# mb_01-1.net
KiCad netlist of a schematic drawn in EAGLE
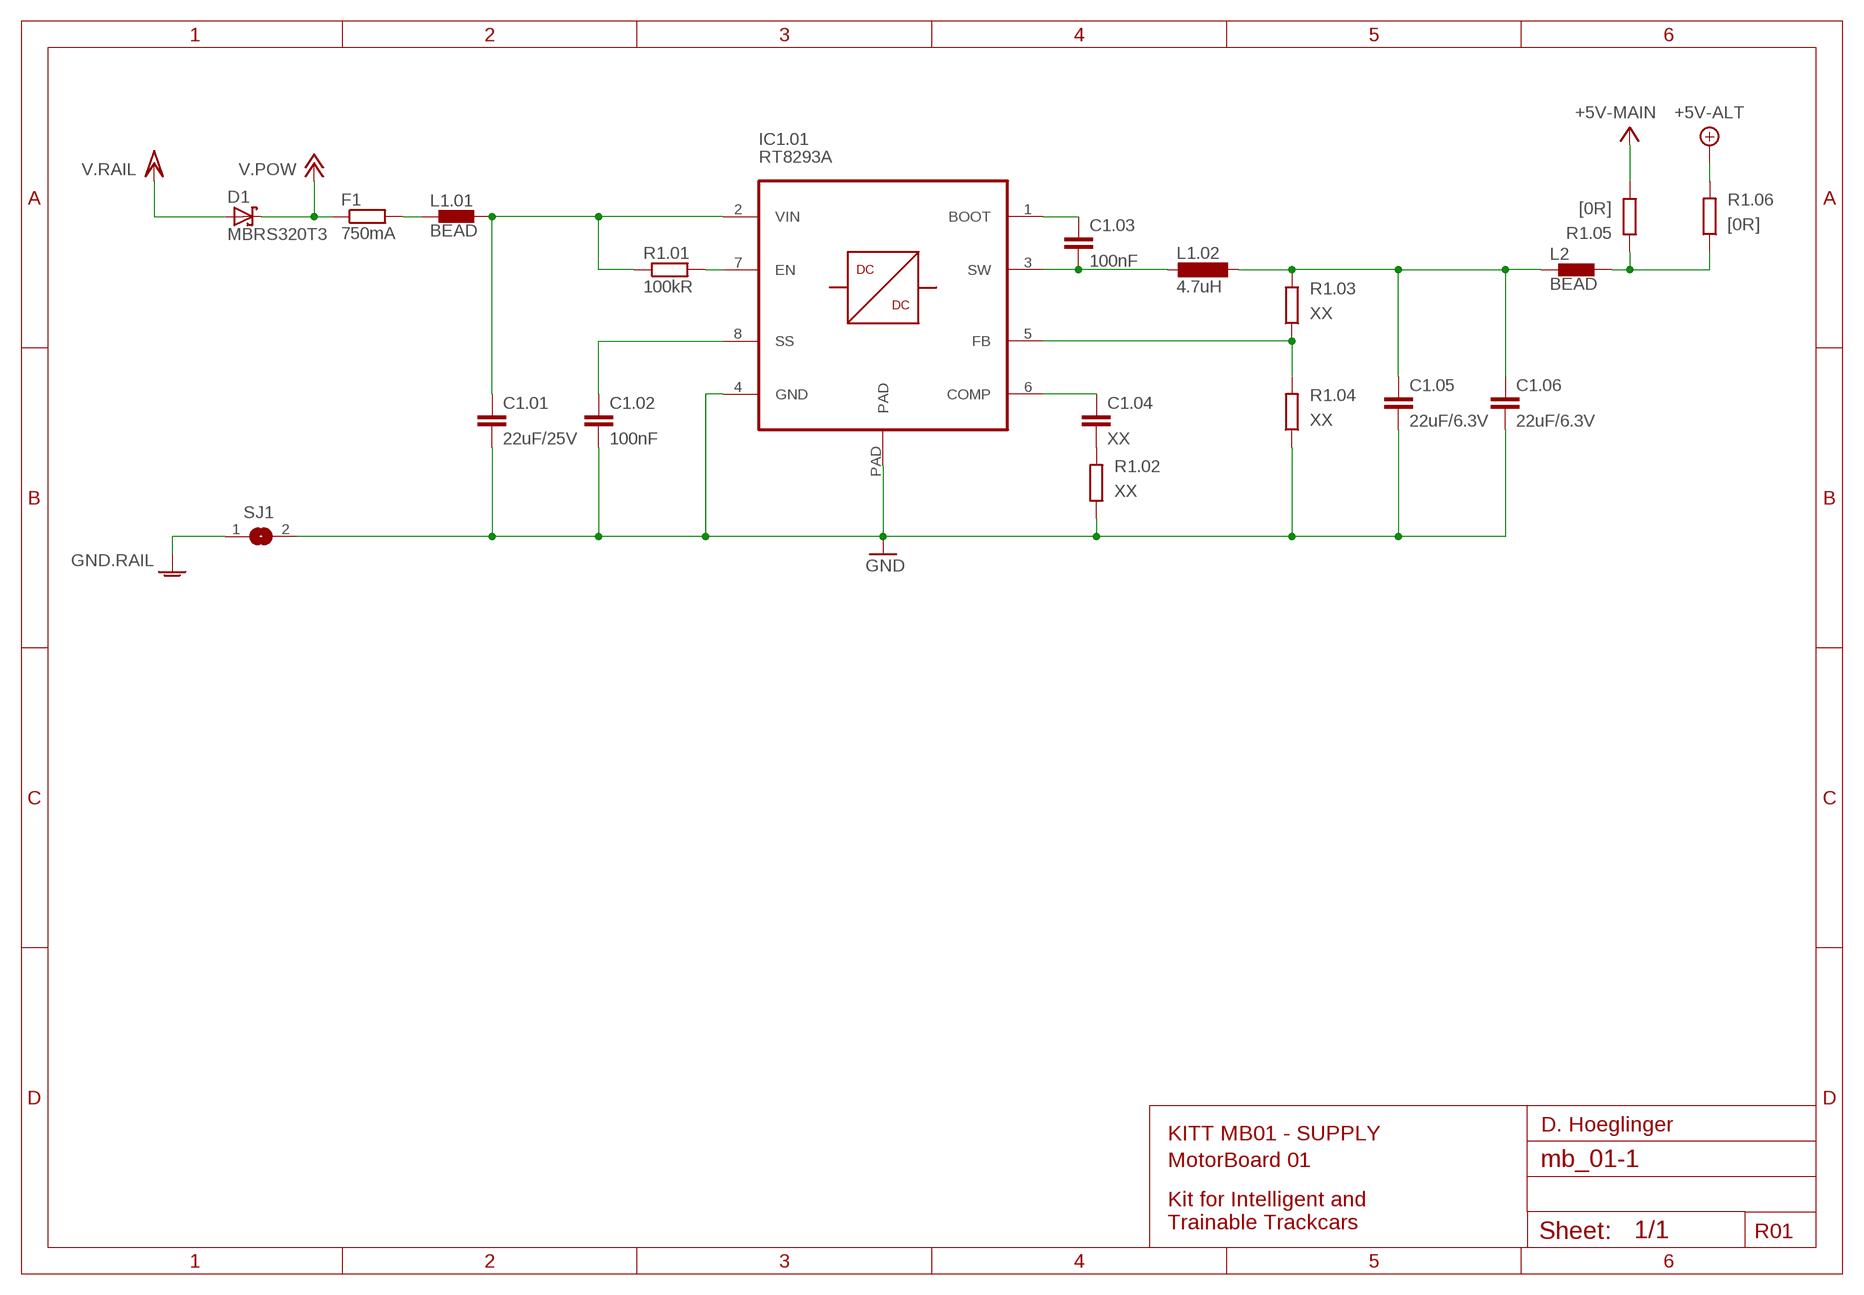
[diagram p0: schematic, sheet 1]

(export (version "E")
  (design (tool "Eeschema 10.0.6"))
  (components
    (comp (ref "C1.01")
      (value "22uF/25V")
      (footprint "eagle-import:C1210K")
      (libsource (lib "eagle-import") (part "C-EUC1210K"))
    )
    (comp (ref "C1.02")
      (value "100nF")
      (footprint "eagle-import:C0402K")
      (libsource (lib "eagle-import") (part "C-EUC0402K"))
    )
    (comp (ref "C1.03")
      (value "100nF")
      (footprint "eagle-import:C0402K")
      (libsource (lib "eagle-import") (part "C-EUC0402K"))
    )
    (comp (ref "C1.04")
      (value "XX")
      (footprint "eagle-import:C0402K")
      (libsource (lib "eagle-import") (part "C-EUC0402K"))
    )
    (comp (ref "C1.05")
      (value "22uF/6.3V")
      (footprint "eagle-import:C1206K")
      (libsource (lib "eagle-import") (part "C-EUC1206K"))
    )
    (comp (ref "C1.06")
      (value "22uF/6.3V")
      (footprint "eagle-import:C1206K")
      (libsource (lib "eagle-import") (part "C-EUC1206K"))
    )
    (comp (ref "D1")
      (value "MBRS320T3")
      (footprint "eagle-import:SMC")
      (libsource (lib "eagle-import") (part "MBRS30T32"))
    )
    (comp (ref "F1")
      (value "750mA")
      (footprint "eagle-import:R0805")
      (libsource (lib "eagle-import") (part "R-EU_R0805"))
    )
    (comp (ref "IC1.01")
      (value "RT8293A")
      (footprint "eagle-import:SOIC-8-PAD")
      (libsource (lib "eagle-import") (part "RT8293A"))
    )
    (comp (ref "L1.01")
      (value "BEAD")
      (footprint "eagle-import:0402")
      (libsource (lib "eagle-import") (part "BLM15HB121SN1"))
    )
    (comp (ref "L1.02")
      (value "4.7uH")
      (footprint "eagle-import:TAIYO-YUDEN.NRS8030T4R7MJGJ")
      (libsource (lib "eagle-import") (part "NRS8030XX"))
    )
    (comp (ref "L2")
      (value "BEAD")
      (footprint "eagle-import:0402")
      (libsource (lib "eagle-import") (part "BLM15HB121SN1"))
    )
    (comp (ref "R1.01")
      (value "100kR")
      (footprint "eagle-import:R0402")
      (libsource (lib "eagle-import") (part "R-EU_R0402"))
    )
    (comp (ref "R1.02")
      (value "XX")
      (footprint "eagle-import:R0402")
      (libsource (lib "eagle-import") (part "R-EU_R0402"))
    )
    (comp (ref "R1.03")
      (value "XX")
      (footprint "eagle-import:R0402")
      (libsource (lib "eagle-import") (part "R-EU_R0402"))
    )
    (comp (ref "R1.04")
      (value "XX")
      (footprint "eagle-import:R0402")
      (libsource (lib "eagle-import") (part "R-EU_R0402"))
    )
    (comp (ref "R1.05")
      (value "[0R]")
      (footprint "eagle-import:R0402")
      (libsource (lib "eagle-import") (part "R-EU_R0402"))
    )
    (comp (ref "R1.06")
      (value "[0R]")
      (footprint "eagle-import:R0402")
      (libsource (lib "eagle-import") (part "R-EU_R0402"))
    )
    (comp (ref "SJ1") (value "SJ") (footprint "eagle-import:SJ") (libsource (lib "eagle-import") (part "SJ")))
  )
  (nets
    (net (code "1") (name "+5V-ALT") (class "Default")
      (node (ref "R1.05") (pin "1") (pinfunction "1_1") (pintype "passive"))
      (node (ref "R1.06") (pin "2") (pinfunction "2_2") (pintype "passive"))
    )
    (net (code "2") (name "GND") (class "Default")
      (node (ref "C1.01") (pin "2") (pinfunction "2_2") (pintype "passive"))
      (node (ref "C1.02") (pin "2") (pinfunction "2_2") (pintype "passive"))
      (node (ref "C1.05") (pin "2") (pinfunction "2_2") (pintype "passive"))
      (node (ref "C1.06") (pin "2") (pinfunction "2_2") (pintype "passive"))
      (node (ref "IC1.01") (pin "4") (pinfunction "GND_4") (pintype "bidirectional"))
      (node (ref "IC1.01") (pin "PAD") (pinfunction "PAD_PAD") (pintype "bidirectional"))
      (node (ref "R1.02") (pin "1") (pinfunction "1_1") (pintype "passive"))
      (node (ref "R1.04") (pin "1") (pinfunction "1_1") (pintype "passive"))
      (node (ref "SJ1") (pin "2") (pinfunction "2_2") (pintype "passive"))
    )
    (net (code "3") (name "GND.RAIL") (class "Default")
      (node (ref "SJ1") (pin "1") (pinfunction "1_1") (pintype "passive"))
    )
    (net (code "4") (name "Net-(C1.04-Pad2)") (class "Default")
      (node (ref "C1.04") (pin "2") (pinfunction "2_2") (pintype "passive"))
      (node (ref "R1.02") (pin "2") (pinfunction "2_2") (pintype "passive"))
    )
    (net (code "5") (name "Net-(C1.05-Pad1)") (class "Default")
      (node (ref "C1.05") (pin "1") (pinfunction "1_1") (pintype "passive"))
      (node (ref "C1.06") (pin "1") (pinfunction "1_1") (pintype "passive"))
      (node (ref "L1.02") (pin "1") (pinfunction "1_1") (pintype "passive"))
      (node (ref "L2") (pin "1") (pinfunction "1_1") (pintype "passive"))
      (node (ref "R1.03") (pin "2") (pinfunction "2_2") (pintype "passive"))
    )
    (net (code "6") (name "Net-(F1-Pad2)") (class "Default")
      (node (ref "F1") (pin "2") (pinfunction "2_2") (pintype "passive"))
      (node (ref "L1.01") (pin "1") (pinfunction "1_1") (pintype "passive"))
    )
    (net (code "7") (name "Net-(IC1.01-BOOT)") (class "Default")
      (node (ref "C1.03") (pin "1") (pinfunction "1_1") (pintype "passive"))
      (node (ref "IC1.01") (pin "1") (pinfunction "BOOT_1") (pintype "bidirectional"))
    )
    (net (code "8") (name "Net-(IC1.01-COMP)") (class "Default")
      (node (ref "C1.04") (pin "1") (pinfunction "1_1") (pintype "passive"))
      (node (ref "IC1.01") (pin "6") (pinfunction "COMP_6") (pintype "bidirectional"))
    )
    (net (code "9") (name "Net-(IC1.01-EN)") (class "Default")
      (node (ref "IC1.01") (pin "7") (pinfunction "EN_7") (pintype "bidirectional"))
      (node (ref "R1.01") (pin "2") (pinfunction "2_2") (pintype "passive"))
    )
    (net (code "10") (name "Net-(IC1.01-FB)") (class "Default")
      (node (ref "IC1.01") (pin "5") (pinfunction "FB_5") (pintype "bidirectional"))
      (node (ref "R1.03") (pin "1") (pinfunction "1_1") (pintype "passive"))
      (node (ref "R1.04") (pin "2") (pinfunction "2_2") (pintype "passive"))
    )
    (net (code "11") (name "Net-(IC1.01-SS)") (class "Default")
      (node (ref "C1.02") (pin "1") (pinfunction "1_1") (pintype "passive"))
      (node (ref "IC1.01") (pin "8") (pinfunction "SS_8") (pintype "bidirectional"))
    )
    (net (code "12") (name "Net-(IC1.01-SW)") (class "Default")
      (node (ref "C1.03") (pin "2") (pinfunction "2_2") (pintype "passive"))
      (node (ref "IC1.01") (pin "3") (pinfunction "SW_3") (pintype "bidirectional"))
      (node (ref "L1.02") (pin "2") (pinfunction "2_2") (pintype "passive"))
    )
    (net (code "13") (name "Net-(IC1.01-VIN)") (class "Default")
      (node (ref "C1.01") (pin "1") (pinfunction "1_1") (pintype "passive"))
      (node (ref "IC1.01") (pin "2") (pinfunction "VIN_2") (pintype "bidirectional"))
      (node (ref "L1.01") (pin "2") (pinfunction "2_2") (pintype "passive"))
      (node (ref "R1.01") (pin "1") (pinfunction "1_1") (pintype "passive"))
    )
    (net (code "14") (name "Net-(L2-Pad2)") (class "Default")
      (node (ref "L2") (pin "2") (pinfunction "2_2") (pintype "passive"))
      (node (ref "R1.05") (pin "2") (pinfunction "2_2") (pintype "passive"))
      (node (ref "R1.06") (pin "1") (pinfunction "1_1") (pintype "passive"))
    )
    (net (code "15") (name "V.POW") (class "Default")
      (node (ref "D1") (pin "C") (pinfunction "C_C") (pintype "passive"))
      (node (ref "F1") (pin "1") (pinfunction "1_1") (pintype "passive"))
    )
    (net (code "16") (name "V.RAIL") (class "Default")
      (node (ref "D1") (pin "A") (pinfunction "A_A") (pintype "passive"))
    )
  )
)
